# Volts_Sample.net
KiCad netlist of a schematic drawn in Altium Designer
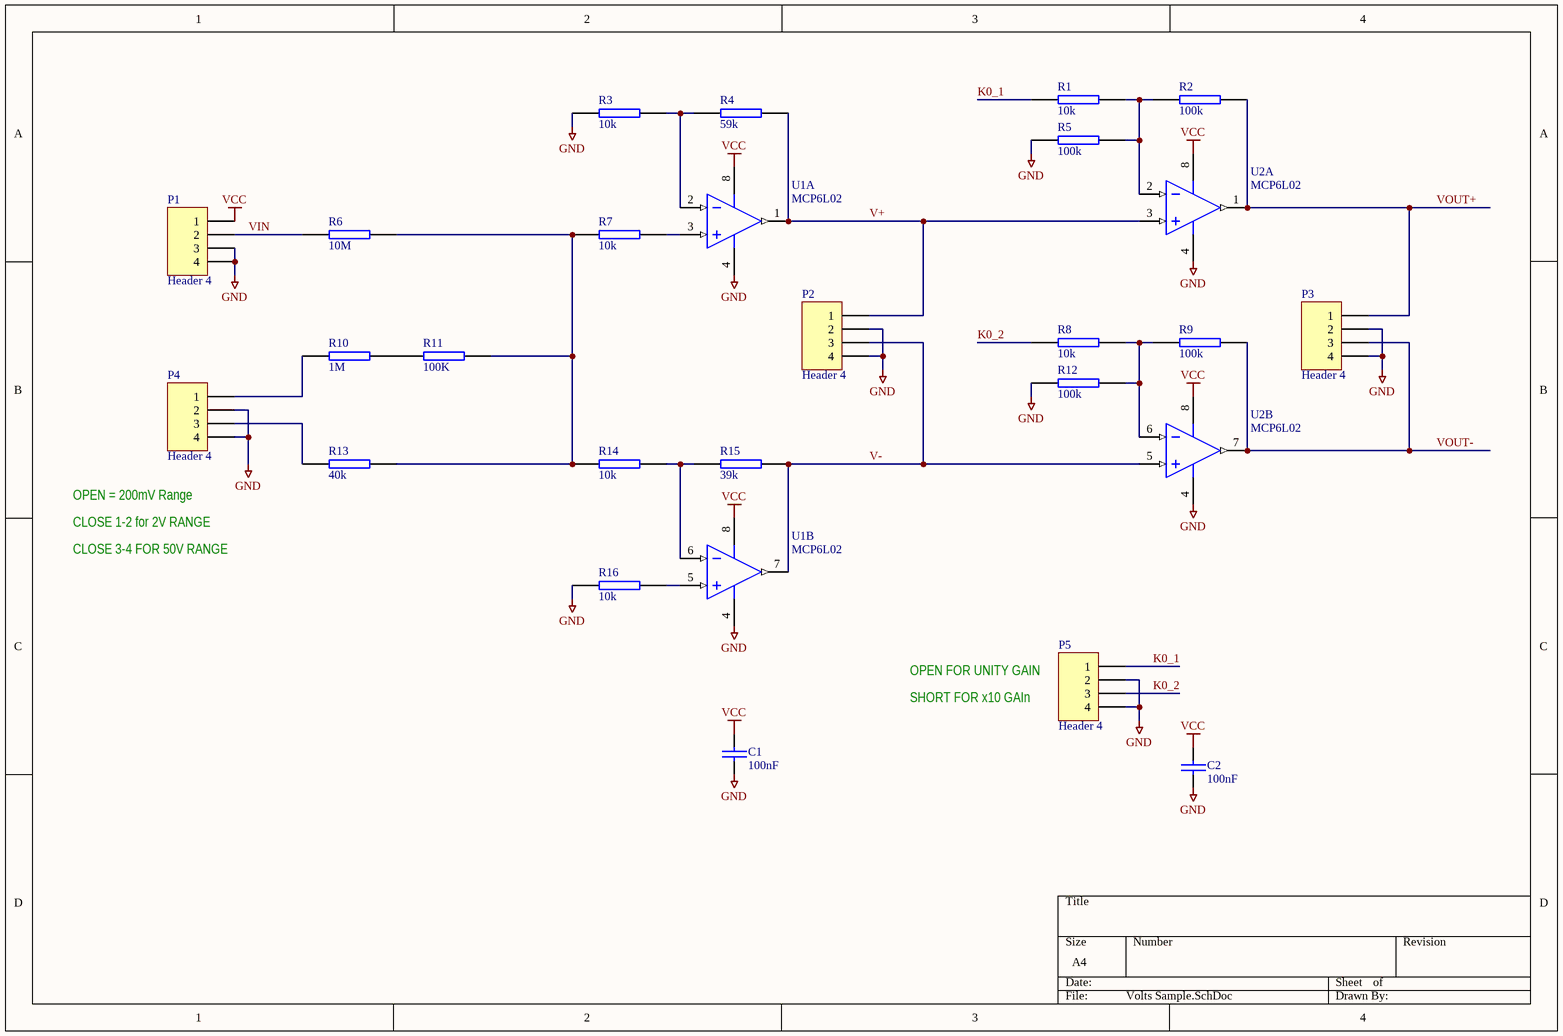
[diagram p0: Volts Sample.SchDoc]

(export (version "E")
  (design (tool "Eeschema 10.0.6"))
  (components
    (comp (ref "C1")
      (value "100nF")
      (footprint "RAD-0.1")
      (description "CAPACITOR SMD 0603")
      (fields
        (field (name "MOUSER PART NO.") "81-GRM155R61C104KA8D")
        (field (name "FARNELL PART NO.") "1414610")
      )
      (libsource (lib "Mi-Call Schematic") (part "CAP"))
    )
    (comp (ref "C2")
      (value "100nF")
      (footprint "RAD-0.1")
      (description "CAPACITOR SMD 0603")
      (fields
        (field (name "MOUSER PART NO.") "81-GRM155R61C104KA8D")
        (field (name "FARNELL PART NO.") "1414610")
      )
      (libsource (lib "Mi-Call Schematic") (part "CAP"))
    )
    (comp (ref "P1")
      (value "Header 4")
      (footprint "HDR1X4")
      (description "Header, 4-Pin")
      (fields (field (name "PUBLISHER") "Altium Limited"))
      (libsource (lib "Miscellaneous Connectors") (part "Header 4"))
    )
    (comp (ref "P2")
      (value "Header 4")
      (footprint "HDR1X4")
      (description "Header, 4-Pin")
      (fields (field (name "PUBLISHER") "Altium Limited"))
      (libsource (lib "Miscellaneous Connectors") (part "Header 4"))
    )
    (comp (ref "P3")
      (value "Header 4")
      (footprint "HDR1X4")
      (description "Header, 4-Pin")
      (fields (field (name "PUBLISHER") "Altium Limited"))
      (libsource (lib "Miscellaneous Connectors") (part "Header 4"))
    )
    (comp (ref "P4")
      (value "Header 4")
      (footprint "HDR1X4")
      (description "Header, 4-Pin")
      (fields (field (name "PUBLISHER") "Altium Limited"))
      (libsource (lib "Miscellaneous Connectors") (part "Header 4"))
    )
    (comp (ref "P5")
      (value "Header 4")
      (footprint "HDR1X4")
      (description "Header, 4-Pin")
      (fields (field (name "PUBLISHER") "Altium Limited"))
      (libsource (lib "Miscellaneous Connectors") (part "Header 4"))
    )
    (comp (ref "R1")
      (value "10k")
      (footprint "AXIAL-0.5")
      (description "RESISTOR SMD 0603 10k")
      (fields (field (name "MOUSER PART NO.") "652-CR0603FX-1002ELF") (field (name "MANUFACTURER") "Bourns"))
      (libsource (lib "NASCO Resistors") (part "RES SMD 0603 10k"))
    )
    (comp (ref "R2")
      (value "100k")
      (footprint "AXIAL-0.5")
      (description "RESISTOR SMD 0603 39k")
      (fields (field (name "MANUFACTURER") "Bourns"))
      (libsource (lib "NASCO Resistors") (part "RES SMD 0603 39k"))
    )
    (comp (ref "R3")
      (value "10k")
      (footprint "AXIAL-0.5")
      (description "RESISTOR SMD 0603 10k")
      (fields (field (name "MOUSER PART NO.") "652-CR0603FX-1002ELF") (field (name "MANUFACTURER") "Bourns"))
      (libsource (lib "NASCO Resistors") (part "RES SMD 0603 10k"))
    )
    (comp (ref "R4")
      (value "59k")
      (footprint "AXIAL-0.5")
      (description "RESISTOR SMD 0603 39k")
      (fields (field (name "MANUFACTURER") "Bourns"))
      (libsource (lib "NASCO Resistors") (part "RES SMD 0603 39k"))
    )
    (comp (ref "R5")
      (value "100k")
      (footprint "AXIAL-0.5")
      (description "RESISTOR SMD 0603 39k")
      (fields (field (name "MANUFACTURER") "Bourns"))
      (libsource (lib "NASCO Resistors") (part "RES SMD 0603 39k"))
    )
    (comp (ref "R6")
      (value "10M")
      (footprint "AXIAL-0.5")
      (description "RESISTOR SMD 0603 39k")
      (fields (field (name "MANUFACTURER") "Bourns"))
      (libsource (lib "NASCO Resistors") (part "RES SMD 0603 39k"))
    )
    (comp (ref "R7")
      (value "10k")
      (footprint "AXIAL-0.5")
      (description "RESISTOR SMD 0603 10k")
      (fields (field (name "MOUSER PART NO.") "652-CR0603FX-1002ELF") (field (name "MANUFACTURER") "Bourns"))
      (libsource (lib "NASCO Resistors") (part "RES SMD 0603 10k"))
    )
    (comp (ref "R8")
      (value "10k")
      (footprint "AXIAL-0.5")
      (description "RESISTOR SMD 0603 10k")
      (fields (field (name "MOUSER PART NO.") "652-CR0603FX-1002ELF") (field (name "MANUFACTURER") "Bourns"))
      (libsource (lib "NASCO Resistors") (part "RES SMD 0603 10k"))
    )
    (comp (ref "R9")
      (value "100k")
      (footprint "AXIAL-0.5")
      (description "RESISTOR SMD 0603 39k")
      (fields (field (name "MANUFACTURER") "Bourns"))
      (libsource (lib "NASCO Resistors") (part "RES SMD 0603 39k"))
    )
    (comp (ref "R10")
      (value "1M")
      (footprint "AXIAL-0.5")
      (description "RESISTOR SMD 0603 39k")
      (fields (field (name "MANUFACTURER") "Bourns"))
      (libsource (lib "NASCO Resistors") (part "RES SMD 0603 39k"))
    )
    (comp (ref "R11")
      (value "100K")
      (footprint "AXIAL-0.5")
      (description "RESISTOR SMD 0603 39k")
      (fields (field (name "MANUFACTURER") "Bourns"))
      (libsource (lib "NASCO Resistors") (part "RES SMD 0603 39k"))
    )
    (comp (ref "R12")
      (value "100k")
      (footprint "AXIAL-0.5")
      (description "RESISTOR SMD 0603 39k")
      (fields (field (name "MANUFACTURER") "Bourns"))
      (libsource (lib "NASCO Resistors") (part "RES SMD 0603 39k"))
    )
    (comp (ref "R13")
      (value "40k")
      (footprint "AXIAL-0.5")
      (description "RESISTOR SMD 0603 39k")
      (fields (field (name "MANUFACTURER") "Bourns"))
      (libsource (lib "NASCO Resistors") (part "RES SMD 0603 39k"))
    )
    (comp (ref "R14")
      (value "10k")
      (footprint "AXIAL-0.5")
      (description "RESISTOR SMD 0603 10k")
      (fields (field (name "MOUSER PART NO.") "652-CR0603FX-1002ELF") (field (name "MANUFACTURER") "Bourns"))
      (libsource (lib "NASCO Resistors") (part "RES SMD 0603 10k"))
    )
    (comp (ref "R15")
      (value "39k")
      (footprint "AXIAL-0.5")
      (description "RESISTOR SMD 0603 39k")
      (fields (field (name "MOUSER PART NO.") "652-CR0603FX-3902ELF") (field (name "MANUFACTURER") "Bourns"))
      (libsource (lib "NASCO Resistors") (part "RES SMD 0603 39k"))
    )
    (comp (ref "R16")
      (value "10k")
      (footprint "AXIAL-0.5")
      (description "RESISTOR SMD 0603 10k")
      (fields (field (name "MOUSER PART NO.") "652-CR0603FX-1002ELF") (field (name "MANUFACTURER") "Bourns"))
      (libsource (lib "NASCO Resistors") (part "RES SMD 0603 10k"))
    )
    (comp (ref "U1") (value "MCP6L02") (footprint "SO-8") (libsource (lib "MCPL02") (part "MCP6L02")))
    (comp (ref "U2") (value "MCP6L02") (footprint "SO-8") (libsource (lib "MCPL02") (part "MCP6L02")))
  )
  (nets
    (net (code "1") (name "/K0_1") (class "Default")
      (node (ref "P5") (pin "1") (pinfunction "1_1") (pintype "passive"))
      (node (ref "R1") (pin "1") (pinfunction "1_1") (pintype "passive"))
    )
    (net (code "2") (name "/K0_2") (class "Default")
      (node (ref "P5") (pin "3") (pinfunction "3_3") (pintype "passive"))
      (node (ref "R8") (pin "1") (pinfunction "1_1") (pintype "passive"))
    )
    (net (code "3") (name "/V+") (class "Default")
      (node (ref "P2") (pin "1") (pinfunction "1_1") (pintype "passive"))
      (node (ref "R4") (pin "2") (pinfunction "2_2") (pintype "passive"))
      (node (ref "U1") (pin "1") (pinfunction "OUTA_1") (pintype "output"))
      (node (ref "U2") (pin "3") (pinfunction "INA+_3") (pintype "input"))
    )
    (net (code "4") (name "/V-") (class "Default")
      (node (ref "P2") (pin "3") (pinfunction "3_3") (pintype "passive"))
      (node (ref "R15") (pin "2") (pinfunction "2_2") (pintype "passive"))
      (node (ref "U1") (pin "7") (pinfunction "OUTB_7") (pintype "output"))
      (node (ref "U2") (pin "5") (pinfunction "INB+_5") (pintype "input"))
    )
    (net (code "5") (name "/VIN") (class "Default")
      (node (ref "P1") (pin "2") (pinfunction "2_2") (pintype "passive"))
      (node (ref "R6") (pin "1") (pinfunction "1_1") (pintype "passive"))
    )
    (net (code "6") (name "/VOUT+") (class "Default")
      (node (ref "P3") (pin "1") (pinfunction "1_1") (pintype "passive"))
      (node (ref "R2") (pin "2") (pinfunction "2_2") (pintype "passive"))
      (node (ref "U2") (pin "1") (pinfunction "OUTA_1") (pintype "output"))
    )
    (net (code "7") (name "/VOUT-") (class "Default")
      (node (ref "P3") (pin "3") (pinfunction "3_3") (pintype "passive"))
      (node (ref "R9") (pin "2") (pinfunction "2_2") (pintype "passive"))
      (node (ref "U2") (pin "7") (pinfunction "OUTB_7") (pintype "output"))
    )
    (net (code "8") (name "GND") (class "Default")
      (node (ref "C1") (pin "2") (pinfunction "2_2") (pintype "passive"))
      (node (ref "C2") (pin "2") (pinfunction "2_2") (pintype "passive"))
      (node (ref "P1") (pin "3") (pinfunction "3_3") (pintype "passive"))
      (node (ref "P1") (pin "4") (pinfunction "4_4") (pintype "passive"))
      (node (ref "P2") (pin "2") (pinfunction "2_2") (pintype "passive"))
      (node (ref "P2") (pin "4") (pinfunction "4_4") (pintype "passive"))
      (node (ref "P3") (pin "2") (pinfunction "2_2") (pintype "passive"))
      (node (ref "P3") (pin "4") (pinfunction "4_4") (pintype "passive"))
      (node (ref "P4") (pin "2") (pinfunction "2_2") (pintype "passive"))
      (node (ref "P4") (pin "4") (pinfunction "4_4") (pintype "passive"))
      (node (ref "P5") (pin "2") (pinfunction "2_2") (pintype "passive"))
      (node (ref "P5") (pin "4") (pinfunction "4_4") (pintype "passive"))
      (node (ref "R12") (pin "1") (pinfunction "1_1") (pintype "passive"))
      (node (ref "R16") (pin "1") (pinfunction "1_1") (pintype "passive"))
      (node (ref "R3") (pin "1") (pinfunction "1_1") (pintype "passive"))
      (node (ref "R5") (pin "1") (pinfunction "1_1") (pintype "passive"))
      (node (ref "U1") (pin "4") (pinfunction "GND_4") (pintype "power_in"))
      (node (ref "U2") (pin "4") (pinfunction "GND_4") (pintype "power_in"))
    )
    (net (code "9") (name "Net-(P4-Pad1)") (class "Default")
      (node (ref "P4") (pin "1") (pinfunction "1_1") (pintype "passive"))
      (node (ref "R10") (pin "1") (pinfunction "1_1") (pintype "passive"))
    )
    (net (code "10") (name "Net-(P4-Pad3)") (class "Default")
      (node (ref "P4") (pin "3") (pinfunction "3_3") (pintype "passive"))
      (node (ref "R13") (pin "1") (pinfunction "1_1") (pintype "passive"))
    )
    (net (code "11") (name "Net-(R10-Pad2)") (class "Default")
      (node (ref "R10") (pin "2") (pinfunction "2_2") (pintype "passive"))
      (node (ref "R11") (pin "1") (pinfunction "1_1") (pintype "passive"))
    )
    (net (code "12") (name "Net-(R11-Pad2)") (class "Default")
      (node (ref "R11") (pin "2") (pinfunction "2_2") (pintype "passive"))
      (node (ref "R13") (pin "2") (pinfunction "2_2") (pintype "passive"))
      (node (ref "R14") (pin "1") (pinfunction "1_1") (pintype "passive"))
      (node (ref "R6") (pin "2") (pinfunction "2_2") (pintype "passive"))
      (node (ref "R7") (pin "1") (pinfunction "1_1") (pintype "passive"))
    )
    (net (code "13") (name "Net-(U1A-INA+)") (class "Default")
      (node (ref "R7") (pin "2") (pinfunction "2_2") (pintype "passive"))
      (node (ref "U1") (pin "3") (pinfunction "INA+_3") (pintype "input"))
    )
    (net (code "14") (name "Net-(U1A-INA-)") (class "Default")
      (node (ref "R3") (pin "2") (pinfunction "2_2") (pintype "passive"))
      (node (ref "R4") (pin "1") (pinfunction "1_1") (pintype "passive"))
      (node (ref "U1") (pin "2") (pinfunction "INA-_2") (pintype "input"))
    )
    (net (code "15") (name "Net-(U1B-INB+)") (class "Default")
      (node (ref "R16") (pin "2") (pinfunction "2_2") (pintype "passive"))
      (node (ref "U1") (pin "5") (pinfunction "INB+_5") (pintype "input"))
    )
    (net (code "16") (name "Net-(U1B-INB-)") (class "Default")
      (node (ref "R14") (pin "2") (pinfunction "2_2") (pintype "passive"))
      (node (ref "R15") (pin "1") (pinfunction "1_1") (pintype "passive"))
      (node (ref "U1") (pin "6") (pinfunction "INB-_6") (pintype "input"))
    )
    (net (code "17") (name "Net-(U2A-INA-)") (class "Default")
      (node (ref "R1") (pin "2") (pinfunction "2_2") (pintype "passive"))
      (node (ref "R2") (pin "1") (pinfunction "1_1") (pintype "passive"))
      (node (ref "R5") (pin "2") (pinfunction "2_2") (pintype "passive"))
      (node (ref "U2") (pin "2") (pinfunction "INA-_2") (pintype "input"))
    )
    (net (code "18") (name "Net-(U2B-INB-)") (class "Default")
      (node (ref "R12") (pin "2") (pinfunction "2_2") (pintype "passive"))
      (node (ref "R8") (pin "2") (pinfunction "2_2") (pintype "passive"))
      (node (ref "R9") (pin "1") (pinfunction "1_1") (pintype "passive"))
      (node (ref "U2") (pin "6") (pinfunction "INB-_6") (pintype "input"))
    )
    (net (code "19") (name "VCC") (class "Default")
      (node (ref "C1") (pin "1") (pinfunction "1_1") (pintype "passive"))
      (node (ref "C2") (pin "1") (pinfunction "1_1") (pintype "passive"))
      (node (ref "P1") (pin "1") (pinfunction "1_1") (pintype "passive"))
      (node (ref "U1") (pin "8") (pinfunction "V+_8") (pintype "power_in"))
      (node (ref "U2") (pin "8") (pinfunction "V+_8") (pintype "power_in"))
    )
  )
)
